# EEZ_Mosfet_pre-regulator_r3B3b.net
KiCad netlist of a schematic drawn in EAGLE
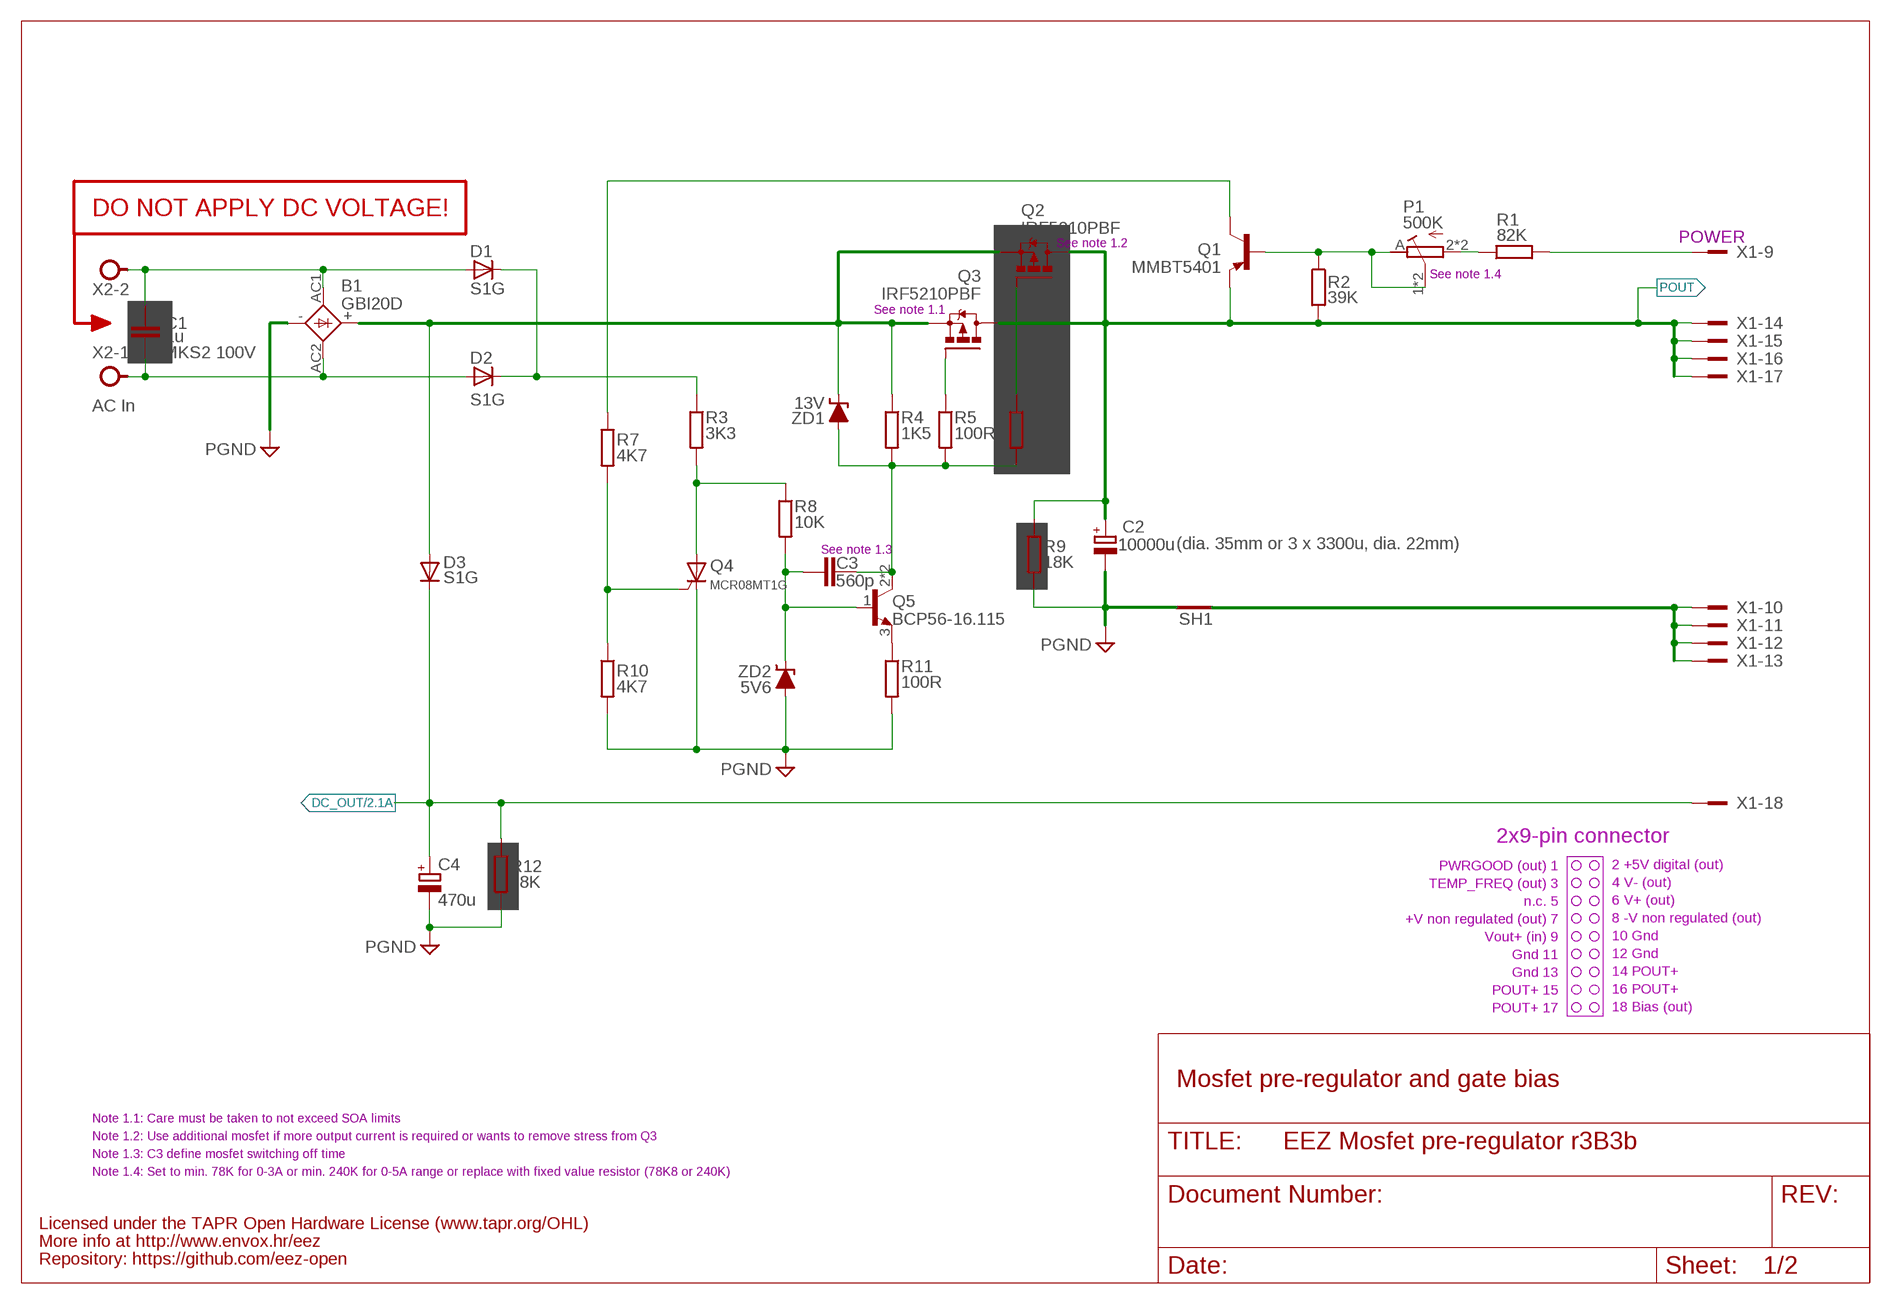
[diagram p0: schematic, sheet 1]
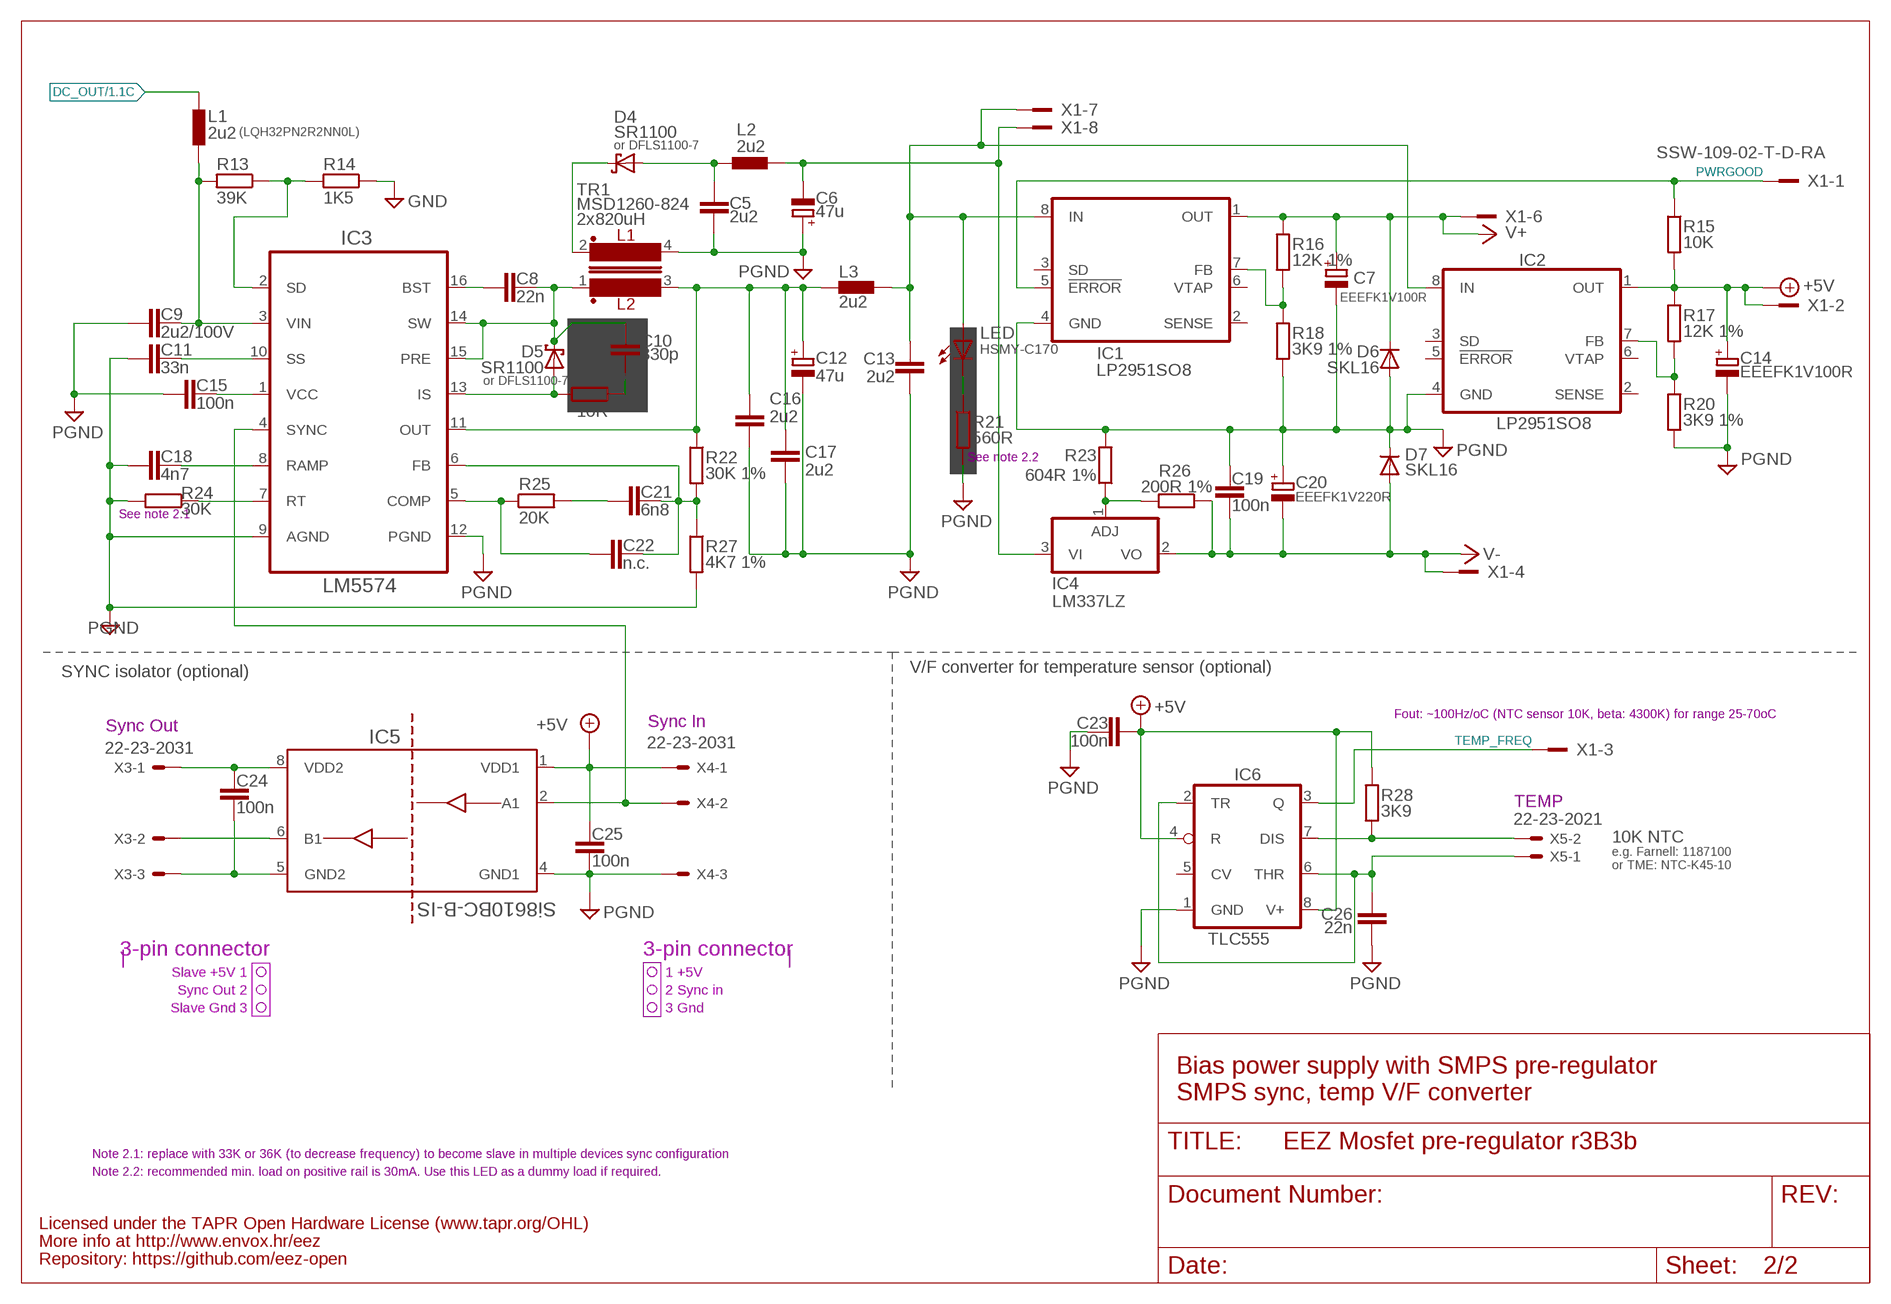
[diagram p1: schematic, sheet 2]

(export (version "E")
  (design (tool "Eeschema 10.0.6"))
  (components
    (comp (ref "C5")
      (value "2u2")
      (footprint "eagle-import:C1210")
      (libsource (lib "eagle-import") (part "C-EUC1210"))
    )
    (comp (ref "C6")
      (value "47u")
      (footprint "eagle-import:CAPAE660X610N_COMBO")
      (libsource (lib "eagle-import") (part "ECAPEEEFK+8.5MM"))
    )
    (comp (ref "C7")
      (value "EEEFK1V100R")
      (footprint "eagle-import:CAPAE430X610N_COMBO")
      (libsource (lib "eagle-import") (part "ECAPEEEFK+5MM"))
    )
    (comp (ref "C8")
      (value "22n")
      (footprint "eagle-import:C0805")
      (libsource (lib "eagle-import") (part "C-EUC0805"))
    )
    (comp (ref "C9")
      (value "2u2/100V")
      (footprint "eagle-import:C1210")
      (libsource (lib "eagle-import") (part "C-EUC1210"))
    )
    (comp (ref "C10")
      (value "330p")
      (footprint "eagle-import:C0805")
      (libsource (lib "eagle-import") (part "C-EUC0805"))
    )
    (comp (ref "C11")
      (value "33n")
      (footprint "eagle-import:C0805")
      (libsource (lib "eagle-import") (part "C-EUC0805"))
    )
    (comp (ref "C12")
      (value "47u")
      (footprint "eagle-import:CAPAE660X610N_COMBO")
      (libsource (lib "eagle-import") (part "ECAPEEEFK+8.5MM"))
    )
    (comp (ref "C13")
      (value "2u2")
      (footprint "eagle-import:C1210")
      (libsource (lib "eagle-import") (part "C-EUC1210"))
    )
    (comp (ref "C14")
      (value "EEEFK1V100R")
      (footprint "eagle-import:CAPAE430X610N_COMBO")
      (libsource (lib "eagle-import") (part "ECAPEEEFK+5MM"))
    )
    (comp (ref "C15")
      (value "100n")
      (footprint "eagle-import:C0805")
      (libsource (lib "eagle-import") (part "C-EUC0805"))
    )
    (comp (ref "C16")
      (value "2u2")
      (footprint "eagle-import:C1210")
      (libsource (lib "eagle-import") (part "C-EUC1210"))
    )
    (comp (ref "C17")
      (value "2u2")
      (footprint "eagle-import:C1210")
      (libsource (lib "eagle-import") (part "C-EUC1210"))
    )
    (comp (ref "C18")
      (value "4n7")
      (footprint "eagle-import:C0805")
      (libsource (lib "eagle-import") (part "C-EUC0805"))
    )
    (comp (ref "C19")
      (value "100n")
      (footprint "eagle-import:C0805")
      (libsource (lib "eagle-import") (part "C-EUC0805"))
    )
    (comp (ref "C20")
      (value "EEEFK1V220R")
      (footprint "eagle-import:CAPAE430X610N_COMBO")
      (libsource (lib "eagle-import") (part "ECAPEEEFK+5MM"))
    )
    (comp (ref "C21")
      (value "6n8")
      (footprint "eagle-import:C0805")
      (libsource (lib "eagle-import") (part "C-EUC0805"))
    )
    (comp (ref "C22")
      (value "n.c.")
      (footprint "eagle-import:C0805")
      (libsource (lib "eagle-import") (part "C-EUC0805"))
    )
    (comp (ref "C23")
      (value "100n")
      (footprint "eagle-import:C0603")
      (libsource (lib "eagle-import") (part "C-EUC0603"))
    )
    (comp (ref "C24")
      (value "100n")
      (footprint "eagle-import:C0603")
      (libsource (lib "eagle-import") (part "C-EUC0603"))
    )
    (comp (ref "C25")
      (value "100n")
      (footprint "eagle-import:C0603")
      (libsource (lib "eagle-import") (part "C-EUC0603"))
    )
    (comp (ref "C26")
      (value "22n")
      (footprint "eagle-import:C0805")
      (libsource (lib "eagle-import") (part "C-EUC0805"))
    )
    (comp (ref "D4")
      (value "SR1100")
      (footprint "eagle-import:DO34+SOD123")
      (libsource (lib "eagle-import") (part "SCHOTTKYDO34+SOD123"))
    )
    (comp (ref "D5")
      (value "SR1100")
      (footprint "eagle-import:DO34+SOD123")
      (libsource (lib "eagle-import") (part "SCHOTTKYDO34+SOD123"))
    )
    (comp (ref "D6")
      (value "SKL16")
      (footprint "eagle-import:DO214AC")
      (libsource (lib "eagle-import") (part "DIODE-DO214AC"))
    )
    (comp (ref "D7")
      (value "SKL16")
      (footprint "eagle-import:DO214AC")
      (libsource (lib "eagle-import") (part "DIODE-DO214AC"))
    )
    (comp (ref "IC1")
      (value "LP2951SO8")
      (footprint "eagle-import:SOIC127P600X175-8N")
      (libsource (lib "eagle-import") (part "LP2951SO8"))
    )
    (comp (ref "IC2")
      (value "LP2951SO8")
      (footprint "eagle-import:SOIC127P600X175-8N")
      (libsource (lib "eagle-import") (part "LP2951SO8"))
    )
    (comp (ref "IC3")
      (value "LM5574")
      (footprint "eagle-import:SOP65P640X110-16N")
      (fields (field (name "MPN") "LM5574MT"))
      (libsource (lib "eagle-import") (part "LM5574"))
    )
    (comp (ref "IC4")
      (value "LM337LZ")
      (footprint "eagle-import:TO92")
      (libsource (lib "eagle-import") (part "337LZLM"))
    )
    (comp (ref "IC5")
      (value "Si8610BC-B-IS")
      (footprint "eagle-import:SOIC127P600X173-8N")
      (libsource (lib "eagle-import") (part "SI8610"))
    )
    (comp (ref "IC6")
      (value "TLC555")
      (footprint "eagle-import:SOIC127P600X175-8N")
      (libsource (lib "eagle-import") (part "LM555SOIC8"))
    )
    (comp (ref "L1")
      (value "2u2")
      (footprint "eagle-import:L1210_COMBO")
      (libsource (lib "eagle-import") (part "L1210COMBO"))
    )
    (comp (ref "L2")
      (value "2u2")
      (footprint "eagle-import:L1210_COMBO")
      (libsource (lib "eagle-import") (part "L1210COMBO"))
    )
    (comp (ref "L3")
      (value "2u2")
      (footprint "eagle-import:L1210_COMBO")
      (libsource (lib "eagle-import") (part "L1210COMBO"))
    )
    (comp (ref "LED")
      (value "HSMY-C170")
      (footprint "eagle-import:CHIPLED_0805")
      (libsource (lib "eagle-import") (part "LEDCHIPLED_0805"))
    )
    (comp (ref "R13")
      (value "39K")
      (footprint "eagle-import:R0805")
      (libsource (lib "eagle-import") (part "R-EU_R0805"))
    )
    (comp (ref "R14")
      (value "1K5")
      (footprint "eagle-import:R0805")
      (libsource (lib "eagle-import") (part "R-EU_R0805"))
    )
    (comp (ref "R15")
      (value "10K")
      (footprint "eagle-import:R0805")
      (libsource (lib "eagle-import") (part "R-EU_R0805"))
    )
    (comp (ref "R16")
      (value "12K 1%")
      (footprint "eagle-import:R0805")
      (libsource (lib "eagle-import") (part "R-EU_R0805"))
    )
    (comp (ref "R17")
      (value "12K 1%")
      (footprint "eagle-import:R0805")
      (libsource (lib "eagle-import") (part "R-EU_R0805"))
    )
    (comp (ref "R18")
      (value "3K9 1%")
      (footprint "eagle-import:R0805")
      (libsource (lib "eagle-import") (part "R-EU_R0805"))
    )
    (comp (ref "R19")
      (value "10R")
      (footprint "eagle-import:R1210")
      (libsource (lib "eagle-import") (part "R-EU_R1210"))
    )
    (comp (ref "R20")
      (value "3K9 1%")
      (footprint "eagle-import:R0805")
      (libsource (lib "eagle-import") (part "R-EU_R0805"))
    )
    (comp (ref "R21")
      (value "560R")
      (footprint "eagle-import:R0805")
      (libsource (lib "eagle-import") (part "R-EU_R0805"))
    )
    (comp (ref "R22")
      (value "30K 1%")
      (footprint "eagle-import:R0805")
      (libsource (lib "eagle-import") (part "R-EU_R0805"))
    )
    (comp (ref "R23")
      (value "604R 1%")
      (footprint "eagle-import:R0805")
      (libsource (lib "eagle-import") (part "R-EU_R0805"))
    )
    (comp (ref "R24")
      (value "30K")
      (footprint "eagle-import:R0805")
      (libsource (lib "eagle-import") (part "R-EU_R0805"))
    )
    (comp (ref "R25")
      (value "20K")
      (footprint "eagle-import:R0805")
      (libsource (lib "eagle-import") (part "R-EU_R0805"))
    )
    (comp (ref "R26")
      (value "200R 1%")
      (footprint "eagle-import:R0805")
      (libsource (lib "eagle-import") (part "R-EU_R0805"))
    )
    (comp (ref "R27")
      (value "4K7 1%")
      (footprint "eagle-import:R0805")
      (libsource (lib "eagle-import") (part "R-EU_R0805"))
    )
    (comp (ref "R28")
      (value "3K9")
      (footprint "eagle-import:R0805")
      (libsource (lib "eagle-import") (part "R-EU_R0805"))
    )
    (comp (ref "TR1")
      (value "MSD1260-824")
      (footprint "eagle-import:MSD1260")
      (libsource (lib "eagle-import") (part "COILCRAFT_MSD1260INV"))
    )
    (comp (ref "X1")
      (value "SSW-109-02-T-D-RA")
      (footprint "eagle-import:SSW-109-02-T-D-RA")
      (fields (field (name "FARNELL") "1804359"))
      (libsource (lib "eagle-import") (part "SSW-109-02-T-D-RA"))
    )
    (comp (ref "X3")
      (value "22-23-2031")
      (footprint "eagle-import:22-23-2031")
      (fields
        (field (name "MF") "MOLEX")
        (field (name "MF_1") "MOLEX")
        (field (name "MPN") "22-23-2031")
        (field (name "OC_FARNELL") "1462950")
        (field (name "OC_NEWARK") "30C0862")
      )
      (libsource (lib "eagle-import") (part "22-23-2031"))
    )
    (comp (ref "X4")
      (value "22-23-2031")
      (footprint "eagle-import:22-23-2031")
      (fields
        (field (name "MF") "MOLEX")
        (field (name "MF_1") "MOLEX")
        (field (name "MPN") "22-23-2031")
        (field (name "OC_FARNELL") "1462950")
        (field (name "OC_NEWARK") "30C0862")
      )
      (libsource (lib "eagle-import") (part "22-23-2031"))
    )
    (comp (ref "X5")
      (value "22-23-2021")
      (footprint "eagle-import:22-23-2021")
      (fields (field (name "MF") "MOLEX"))
      (libsource (lib "eagle-import") (part "22-23-2021"))
    )
    (comp (ref "B1")
      (value "GBI20D")
      (footprint "eagle-import:GBI20")
      (libsource (lib "eagle-import") (part "BRIDGEDIOTEC"))
    )
    (comp (ref "C1")
      (value "1u")
      (footprint "eagle-import:C050-075X075")
      (libsource (lib "eagle-import") (part "C-EU050-075X075"))
    )
    (comp (ref "C2")
      (value "10000u")
      (footprint "eagle-import:ED35D+3XED22.5_COMBO")
      (libsource (lib "eagle-import") (part "ECAP35+3X22.5"))
    )
    (comp (ref "C3")
      (value "560p")
      (footprint "eagle-import:C0805")
      (libsource (lib "eagle-import") (part "C-EUC0805"))
    )
    (comp (ref "C4")
      (value "470u")
      (footprint "eagle-import:ECAP5_13")
      (libsource (lib "eagle-import") (part "ECAP5G_13MM"))
    )
    (comp (ref "D1")
      (value "S1G")
      (footprint "eagle-import:DO214AC")
      (libsource (lib "eagle-import") (part "DIODE-DO214AC"))
    )
    (comp (ref "D2")
      (value "S1G")
      (footprint "eagle-import:DO214AC")
      (libsource (lib "eagle-import") (part "DIODE-DO214AC"))
    )
    (comp (ref "D3")
      (value "S1G")
      (footprint "eagle-import:DO214AC")
      (libsource (lib "eagle-import") (part "DIODE-DO214AC"))
    )
    (comp (ref "P1")
      (value "500K")
      (footprint "eagle-import:R_TRIM+R0805")
      (libsource (lib "eagle-import") (part "R_TRIM_MIX0805"))
    )
    (comp (ref "Q1")
      (value "MMBT5401")
      (footprint "eagle-import:SOT23-BEC")
      (libsource (lib "eagle-import") (part "-PNP-SOT23-BECBC856B"))
    )
    (comp (ref "Q2")
      (value "IRF5210PBF")
      (footprint "eagle-import:TO220B-VMOS")
      (libsource (lib "eagle-import") (part "IRF9640"))
    )
    (comp (ref "Q3")
      (value "IRF5210PBF")
      (footprint "eagle-import:TO220B-VMOS")
      (libsource (lib "eagle-import") (part "IRF9640"))
    )
    (comp (ref "Q4")
      (value "MCR08MT1G")
      (footprint "eagle-import:SOT230P700X180-4N")
      (libsource (lib "eagle-import") (part "MCR08MT1G"))
    )
    (comp (ref "Q5")
      (value "BCP56-16.115")
      (footprint "eagle-import:SOT230P700X180-4N")
      (libsource (lib "eagle-import") (part "BCP56"))
    )
    (comp (ref "R1")
      (value "82K")
      (footprint "eagle-import:R0805")
      (libsource (lib "eagle-import") (part "R-EU_R0805"))
    )
    (comp (ref "R2")
      (value "39K")
      (footprint "eagle-import:R0805")
      (libsource (lib "eagle-import") (part "R-EU_R0805"))
    )
    (comp (ref "R3")
      (value "3K3")
      (footprint "eagle-import:R0805")
      (libsource (lib "eagle-import") (part "R-EU_R0805"))
    )
    (comp (ref "R4")
      (value "1K5")
      (footprint "eagle-import:R0805")
      (libsource (lib "eagle-import") (part "R-EU_R0805"))
    )
    (comp (ref "R5")
      (value "100R")
      (footprint "eagle-import:R0805")
      (libsource (lib "eagle-import") (part "R-EU_R0805"))
    )
    (comp (ref "R6")
      (value "100R")
      (footprint "eagle-import:R0805")
      (libsource (lib "eagle-import") (part "R-EU_R0805"))
    )
    (comp (ref "R7")
      (value "4K7")
      (footprint "eagle-import:R0805")
      (libsource (lib "eagle-import") (part "R-EU_R0805"))
    )
    (comp (ref "R8")
      (value "10K")
      (footprint "eagle-import:R0805")
      (libsource (lib "eagle-import") (part "R-EU_R0805"))
    )
    (comp (ref "R9")
      (value "18K")
      (footprint "eagle-import:R0805")
      (libsource (lib "eagle-import") (part "R-EU_R0805"))
    )
    (comp (ref "R10")
      (value "4K7")
      (footprint "eagle-import:R0805")
      (libsource (lib "eagle-import") (part "R-EU_R0805"))
    )
    (comp (ref "R11")
      (value "100R")
      (footprint "eagle-import:R0805")
      (libsource (lib "eagle-import") (part "R-EU_R0805"))
    )
    (comp (ref "R12")
      (value "18K")
      (footprint "eagle-import:R0805")
      (libsource (lib "eagle-import") (part "R-EU_R0805"))
    )
    (comp (ref "SH1")
      (value "SHORTH")
      (footprint "eagle-import:SHORT_2")
      (libsource (lib "eagle-import") (part "SHORTH"))
    )
    (comp (ref "X2")
      (value "AC In")
      (footprint "eagle-import:TBLOCK5.0_2")
      (libsource (lib "eagle-import") (part "TBLOCK5.0_2A"))
    )
    (comp (ref "ZD1")
      (value "13V")
      (footprint "eagle-import:MINIMELF")
      (libsource (lib "eagle-import") (part "ZENER-DIODEMINIMELF"))
    )
    (comp (ref "ZD2")
      (value "5V6")
      (footprint "eagle-import:MINIMELF")
      (libsource (lib "eagle-import") (part "ZENER-DIODEMINIMELF"))
    )
  )
  (nets
    (net (code "1") (name "+5V") (class "Default")
      (node (ref "C14") (pin "1") (pinfunction "+_1") (pintype "passive"))
      (node (ref "C14") (pin "1.1") (pinfunction "+_1.1") (pintype "passive"))
      (node (ref "C23") (pin "1") (pinfunction "1_1") (pintype "passive"))
      (node (ref "C25") (pin "1") (pinfunction "1_1") (pintype "passive"))
      (node (ref "IC2") (pin "1") (pinfunction "OUT_1") (pintype "output"))
      (node (ref "IC5") (pin "1") (pinfunction "VDD1_1") (pintype "power_in"))
      (node (ref "IC6") (pin "4") (pinfunction "R_4") (pintype "input"))
      (node (ref "IC6") (pin "8") (pinfunction "V+_8") (pintype "power_in"))
      (node (ref "R15") (pin "2") (pinfunction "2_2") (pintype "passive"))
      (node (ref "R17") (pin "1") (pinfunction "1_1") (pintype "passive"))
      (node (ref "R28") (pin "2") (pinfunction "2_2") (pintype "passive"))
      (node (ref "X1") (pin "2") (pinfunction "KL_2") (pintype "passive"))
      (node (ref "X4") (pin "1") (pinfunction "S_1") (pintype "passive"))
    )
    (net (code "2") (name "DC_OUT") (class "Default")
      (node (ref "C4") (pin "+") (pinfunction "+_+") (pintype "passive"))
      (node (ref "D3") (pin "C") (pinfunction "C_C") (pintype "passive"))
      (node (ref "L1") (pin "1") (pinfunction "1_1") (pintype "passive"))
      (node (ref "L1") (pin "1.1") (pinfunction "1_1.1") (pintype "passive"))
      (node (ref "R12") (pin "1") (pinfunction "1_1") (pintype "passive"))
      (node (ref "X1") (pin "18") (pinfunction "KL_18") (pintype "passive"))
    )
    (net (code "3") (name "GND") (class "Default")
      (node (ref "B1") (pin "-") (pinfunction "-_-") (pintype "passive"))
      (node (ref "C11") (pin "2") (pinfunction "2_2") (pintype "passive"))
      (node (ref "C12") (pin "2") (pinfunction "-_2") (pintype "passive"))
      (node (ref "C12") (pin "2.1") (pinfunction "-_2.1") (pintype "passive"))
      (node (ref "C13") (pin "2") (pinfunction "2_2") (pintype "passive"))
      (node (ref "C14") (pin "2") (pinfunction "-_2") (pintype "passive"))
      (node (ref "C14") (pin "2.1") (pinfunction "-_2.1") (pintype "passive"))
      (node (ref "C15") (pin "1") (pinfunction "1_1") (pintype "passive"))
      (node (ref "C16") (pin "2") (pinfunction "2_2") (pintype "passive"))
      (node (ref "C17") (pin "2") (pinfunction "2_2") (pintype "passive"))
      (node (ref "C18") (pin "1") (pinfunction "1_1") (pintype "passive"))
      (node (ref "C19") (pin "1") (pinfunction "1_1") (pintype "passive"))
      (node (ref "C2") (pin "-") (pinfunction "-_-") (pintype "passive"))
      (node (ref "C2") (pin "-1") (pinfunction "-_-1") (pintype "passive"))
      (node (ref "C2") (pin "-2") (pinfunction "-_-2") (pintype "passive"))
      (node (ref "C2") (pin "-3") (pinfunction "-_-3") (pintype "passive"))
      (node (ref "C20") (pin "1") (pinfunction "+_1") (pintype "passive"))
      (node (ref "C20") (pin "1.1") (pinfunction "+_1.1") (pintype "passive"))
      (node (ref "C23") (pin "2") (pinfunction "2_2") (pintype "passive"))
      (node (ref "C25") (pin "2") (pinfunction "2_2") (pintype "passive"))
      (node (ref "C26") (pin "1") (pinfunction "1_1") (pintype "passive"))
      (node (ref "C4") (pin "-") (pinfunction "-_-") (pintype "passive"))
      (node (ref "C5") (pin "2") (pinfunction "2_2") (pintype "passive"))
      (node (ref "C6") (pin "1") (pinfunction "+_1") (pintype "passive"))
      (node (ref "C6") (pin "1.1") (pinfunction "+_1.1") (pintype "passive"))
      (node (ref "C7") (pin "2") (pinfunction "-_2") (pintype "passive"))
      (node (ref "C7") (pin "2.1") (pinfunction "-_2.1") (pintype "passive"))
      (node (ref "C9") (pin "2") (pinfunction "2_2") (pintype "passive"))
      (node (ref "D6") (pin "A") (pinfunction "A_A") (pintype "passive"))
      (node (ref "D7") (pin "C") (pinfunction "C_C") (pintype "passive"))
      (node (ref "IC1") (pin "4") (pinfunction "GND_4") (pintype "passive"))
      (node (ref "IC2") (pin "4") (pinfunction "GND_4") (pintype "passive"))
      (node (ref "IC3") (pin "12") (pinfunction "PGND_12") (pintype "passive"))
      (node (ref "IC3") (pin "9") (pinfunction "AGND_9") (pintype "passive"))
      (node (ref "IC5") (pin "4") (pinfunction "GND1_4") (pintype "power_in"))
      (node (ref "IC6") (pin "1") (pinfunction "GND_1") (pintype "power_in"))
      (node (ref "Q4") (pin "1") (pinfunction "C_1") (pintype "passive"))
      (node (ref "R10") (pin "2") (pinfunction "2_2") (pintype "passive"))
      (node (ref "R11") (pin "2") (pinfunction "2_2") (pintype "passive"))
      (node (ref "R12") (pin "2") (pinfunction "2_2") (pintype "passive"))
      (node (ref "R14") (pin "1") (pinfunction "1_1") (pintype "passive"))
      (node (ref "R18") (pin "2") (pinfunction "2_2") (pintype "passive"))
      (node (ref "R20") (pin "2") (pinfunction "2_2") (pintype "passive"))
      (node (ref "R21") (pin "2") (pinfunction "2_2") (pintype "passive"))
      (node (ref "R23") (pin "2") (pinfunction "2_2") (pintype "passive"))
      (node (ref "R24") (pin "2") (pinfunction "2_2") (pintype "passive"))
      (node (ref "R27") (pin "2") (pinfunction "2_2") (pintype "passive"))
      (node (ref "R9") (pin "2") (pinfunction "2_2") (pintype "passive"))
      (node (ref "SH1") (pin "2") (pinfunction "GND_B_2") (pintype "bidirectional"))
      (node (ref "TR1") (pin "4") (pinfunction "4_4") (pintype "passive"))
      (node (ref "X4") (pin "3") (pinfunction "S_3") (pintype "passive"))
      (node (ref "ZD2") (pin "A") (pinfunction "A_A") (pintype "passive"))
    )
    (net (code "4") (name "Net-(B1-Pad+)") (class "Default")
      (node (ref "B1") (pin "+") (pinfunction "+_+") (pintype "passive"))
      (node (ref "D3") (pin "A") (pinfunction "A_A") (pintype "passive"))
      (node (ref "Q2") (pin "S") (pinfunction "S_S") (pintype "passive"))
      (node (ref "Q3") (pin "S") (pinfunction "S_S") (pintype "passive"))
      (node (ref "R4") (pin "1") (pinfunction "1_1") (pintype "passive"))
      (node (ref "ZD1") (pin "C") (pinfunction "C_C") (pintype "passive"))
    )
    (net (code "5") (name "Net-(B1-PadAC2)") (class "Default")
      (node (ref "B1") (pin "AC2") (pinfunction "AC2_AC2") (pintype "passive"))
      (node (ref "C1") (pin "2") (pinfunction "2_2") (pintype "passive"))
      (node (ref "D2") (pin "A") (pinfunction "A_A") (pintype "passive"))
      (node (ref "X2") (pin "1") (pinfunction "1_1") (pintype "bidirectional"))
    )
    (net (code "6") (name "Net-(C3-Pad1)") (class "Default")
      (node (ref "C3") (pin "1") (pinfunction "1_1") (pintype "passive"))
      (node (ref "Q5") (pin "2") (pinfunction "C_2") (pintype "passive"))
      (node (ref "Q5") (pin "4") (pinfunction "C_4") (pintype "passive"))
      (node (ref "R4") (pin "2") (pinfunction "2_2") (pintype "passive"))
      (node (ref "R5") (pin "2") (pinfunction "2_2") (pintype "passive"))
      (node (ref "R6") (pin "2") (pinfunction "2_2") (pintype "passive"))
      (node (ref "ZD1") (pin "A") (pinfunction "A_A") (pintype "passive"))
    )
    (net (code "7") (name "Net-(C5-Pad1)") (class "Default")
      (node (ref "C5") (pin "1") (pinfunction "1_1") (pintype "passive"))
      (node (ref "D4") (pin "A") (pinfunction "A_A") (pintype "passive"))
      (node (ref "D4") (pin "A.1") (pinfunction "A_A.1") (pintype "passive"))
      (node (ref "L2") (pin "1") (pinfunction "1_1") (pintype "passive"))
      (node (ref "L2") (pin "1.1") (pinfunction "1_1.1") (pintype "passive"))
    )
    (net (code "8") (name "Net-(C10-Pad2)") (class "Default")
      (node (ref "C10") (pin "2") (pinfunction "2_2") (pintype "passive"))
      (node (ref "R19") (pin "2") (pinfunction "2_2") (pintype "passive"))
    )
    (net (code "9") (name "Net-(C21-Pad2)") (class "Default")
      (node (ref "C21") (pin "2") (pinfunction "2_2") (pintype "passive"))
      (node (ref "R25") (pin "2") (pinfunction "2_2") (pintype "passive"))
    )
    (net (code "10") (name "Net-(D1-PadC)") (class "Default")
      (node (ref "D1") (pin "C") (pinfunction "C_C") (pintype "passive"))
      (node (ref "D2") (pin "C") (pinfunction "C_C") (pintype "passive"))
      (node (ref "R3") (pin "1") (pinfunction "1_1") (pintype "passive"))
    )
    (net (code "11") (name "Net-(D4-C-PadC.1)") (class "Default")
      (node (ref "D4") (pin "C") (pinfunction "C_C") (pintype "passive"))
      (node (ref "D4") (pin "C.1") (pinfunction "C_C.1") (pintype "passive"))
      (node (ref "TR1") (pin "2") (pinfunction "2_2") (pintype "passive"))
    )
    (net (code "12") (name "Net-(IC1-FB)") (class "Default")
      (node (ref "IC1") (pin "7") (pinfunction "FB_7") (pintype "input"))
      (node (ref "R16") (pin "2") (pinfunction "2_2") (pintype "passive"))
      (node (ref "R18") (pin "1") (pinfunction "1_1") (pintype "passive"))
    )
    (net (code "13") (name "Net-(IC1-IN)") (class "Default")
      (node (ref "C13") (pin "1") (pinfunction "1_1") (pintype "passive"))
      (node (ref "IC1") (pin "8") (pinfunction "IN_8") (pintype "power_in"))
      (node (ref "IC2") (pin "8") (pinfunction "IN_8") (pintype "power_in"))
      (node (ref "L3") (pin "2") (pinfunction "2_2") (pintype "passive"))
      (node (ref "L3") (pin "2.1") (pinfunction "2_2.1") (pintype "passive"))
      (node (ref "LED") (pin "A") (pinfunction "A_A") (pintype "passive"))
      (node (ref "X1") (pin "7") (pinfunction "KL_7") (pintype "passive"))
    )
    (net (code "14") (name "Net-(IC2-FB)") (class "Default")
      (node (ref "IC2") (pin "7") (pinfunction "FB_7") (pintype "input"))
      (node (ref "R17") (pin "2") (pinfunction "2_2") (pintype "passive"))
      (node (ref "R20") (pin "1") (pinfunction "1_1") (pintype "passive"))
    )
    (net (code "15") (name "Net-(IC3-BST)") (class "Default")
      (node (ref "C8") (pin "2") (pinfunction "2_2") (pintype "passive"))
      (node (ref "IC3") (pin "16") (pinfunction "BST_16") (pintype "input"))
    )
    (net (code "16") (name "Net-(IC3-COMP)") (class "Default")
      (node (ref "C22") (pin "2") (pinfunction "2_2") (pintype "passive"))
      (node (ref "IC3") (pin "5") (pinfunction "COMP_5") (pintype "input"))
      (node (ref "R25") (pin "1") (pinfunction "1_1") (pintype "passive"))
    )
    (net (code "17") (name "Net-(IC3-FB)") (class "Default")
      (node (ref "C21") (pin "1") (pinfunction "1_1") (pintype "passive"))
      (node (ref "C22") (pin "1") (pinfunction "1_1") (pintype "passive"))
      (node (ref "IC3") (pin "6") (pinfunction "FB_6") (pintype "input"))
      (node (ref "R22") (pin "2") (pinfunction "2_2") (pintype "passive"))
      (node (ref "R27") (pin "1") (pinfunction "1_1") (pintype "passive"))
    )
    (net (code "18") (name "Net-(IC3-IS)") (class "Default")
      (node (ref "D5") (pin "A") (pinfunction "A_A") (pintype "passive"))
      (node (ref "D5") (pin "A.1") (pinfunction "A_A.1") (pintype "passive"))
      (node (ref "IC3") (pin "13") (pinfunction "IS_13") (pintype "input"))
      (node (ref "R19") (pin "1") (pinfunction "1_1") (pintype "passive"))
    )
    (net (code "19") (name "Net-(IC3-OUT)") (class "Default")
      (node (ref "C12") (pin "1") (pinfunction "+_1") (pintype "passive"))
      (node (ref "C12") (pin "1.1") (pinfunction "+_1.1") (pintype "passive"))
      (node (ref "C16") (pin "1") (pinfunction "1_1") (pintype "passive"))
      (node (ref "C17") (pin "1") (pinfunction "1_1") (pintype "passive"))
      (node (ref "IC3") (pin "11") (pinfunction "OUT_11") (pintype "output"))
      (node (ref "L3") (pin "1") (pinfunction "1_1") (pintype "passive"))
      (node (ref "L3") (pin "1.1") (pinfunction "1_1.1") (pintype "passive"))
      (node (ref "R22") (pin "1") (pinfunction "1_1") (pintype "passive"))
      (node (ref "TR1") (pin "3") (pinfunction "3_3") (pintype "passive"))
    )
    (net (code "20") (name "Net-(IC3-PRE)") (class "Default")
      (node (ref "C10") (pin "1") (pinfunction "1_1") (pintype "passive"))
      (node (ref "C8") (pin "1") (pinfunction "1_1") (pintype "passive"))
      (node (ref "D5") (pin "C") (pinfunction "C_C") (pintype "passive"))
      (node (ref "D5") (pin "C.1") (pinfunction "C_C.1") (pintype "passive"))
      (node (ref "IC3") (pin "14") (pinfunction "SW_14") (pintype "output"))
      (node (ref "IC3") (pin "15") (pinfunction "PRE_15") (pintype "input"))
      (node (ref "TR1") (pin "1") (pinfunction "1_1") (pintype "passive"))
    )
    (net (code "21") (name "Net-(IC3-RAMP)") (class "Default")
      (node (ref "C18") (pin "2") (pinfunction "2_2") (pintype "passive"))
      (node (ref "IC3") (pin "8") (pinfunction "RAMP_8") (pintype "input"))
    )
    (net (code "22") (name "Net-(IC3-RT)") (class "Default")
      (node (ref "IC3") (pin "7") (pinfunction "RT_7") (pintype "input"))
      (node (ref "R24") (pin "1") (pinfunction "1_1") (pintype "passive"))
    )
    (net (code "23") (name "Net-(IC3-SD)") (class "Default")
      (node (ref "IC3") (pin "2") (pinfunction "SD_2") (pintype "input"))
      (node (ref "R13") (pin "1") (pinfunction "1_1") (pintype "passive"))
      (node (ref "R14") (pin "2") (pinfunction "2_2") (pintype "passive"))
    )
    (net (code "24") (name "Net-(IC3-SS)") (class "Default")
      (node (ref "C11") (pin "1") (pinfunction "1_1") (pintype "passive"))
      (node (ref "IC3") (pin "10") (pinfunction "SS_10") (pintype "input"))
    )
    (net (code "25") (name "Net-(IC3-SYNC)") (class "Default")
      (node (ref "IC3") (pin "4") (pinfunction "SYNC_4") (pintype "input"))
      (node (ref "IC5") (pin "2") (pinfunction "A1_2") (pintype "input"))
      (node (ref "X4") (pin "2") (pinfunction "S_2") (pintype "passive"))
    )
    (net (code "26") (name "Net-(IC3-VCC)") (class "Default")
      (node (ref "C15") (pin "2") (pinfunction "2_2") (pintype "passive"))
      (node (ref "IC3") (pin "1") (pinfunction "VCC_1") (pintype "power_in"))
    )
    (net (code "27") (name "Net-(IC3-VIN)") (class "Default")
      (node (ref "C9") (pin "1") (pinfunction "1_1") (pintype "passive"))
      (node (ref "IC3") (pin "3") (pinfunction "VIN_3") (pintype "input"))
      (node (ref "L1") (pin "2") (pinfunction "2_2") (pintype "passive"))
      (node (ref "L1") (pin "2.1") (pinfunction "2_2.1") (pintype "passive"))
      (node (ref "R13") (pin "2") (pinfunction "2_2") (pintype "passive"))
    )
    (net (code "28") (name "Net-(IC4-ADJ)") (class "Default")
      (node (ref "IC4") (pin "1") (pinfunction "ADJ_1") (pintype "input"))
      (node (ref "R23") (pin "1") (pinfunction "1_1") (pintype "passive"))
      (node (ref "R26") (pin "2") (pinfunction "2_2") (pintype "passive"))
    )
    (net (code "29") (name "Net-(IC4-VI)") (class "Default")
      (node (ref "C6") (pin "2") (pinfunction "-_2") (pintype "passive"))
      (node (ref "C6") (pin "2.1") (pinfunction "-_2.1") (pintype "passive"))
      (node (ref "IC4") (pin "3") (pinfunction "VI_3") (pintype "input"))
      (node (ref "L2") (pin "2") (pinfunction "2_2") (pintype "passive"))
      (node (ref "L2") (pin "2.1") (pinfunction "2_2.1") (pintype "passive"))
      (node (ref "X1") (pin "8") (pinfunction "KL_8") (pintype "passive"))
    )
    (net (code "30") (name "Net-(IC5-B1)") (class "Default")
      (node (ref "IC5") (pin "6") (pinfunction "B1_6") (pintype "output"))
      (node (ref "X3") (pin "2") (pinfunction "S_2") (pintype "passive"))
    )
    (net (code "31") (name "Net-(IC5-GND2)") (class "Default")
      (node (ref "C24") (pin "2") (pinfunction "2_2") (pintype "passive"))
      (node (ref "IC5") (pin "5") (pinfunction "GND2_5") (pintype "power_in"))
      (node (ref "X3") (pin "3") (pinfunction "S_3") (pintype "passive"))
    )
    (net (code "32") (name "Net-(IC5-VDD2)") (class "Default")
      (node (ref "C24") (pin "1") (pinfunction "1_1") (pintype "passive"))
      (node (ref "IC5") (pin "8") (pinfunction "VDD2_8") (pintype "power_in"))
      (node (ref "X3") (pin "1") (pinfunction "S_1") (pintype "passive"))
    )
    (net (code "33") (name "Net-(IC6-DIS)") (class "Default")
      (node (ref "IC6") (pin "7") (pinfunction "DIS_7") (pintype "input"))
      (node (ref "R28") (pin "1") (pinfunction "1_1") (pintype "passive"))
      (node (ref "X5") (pin "2") (pinfunction "S_2") (pintype "passive"))
    )
    (net (code "34") (name "Net-(IC6-THR)") (class "Default")
      (node (ref "C26") (pin "2") (pinfunction "2_2") (pintype "passive"))
      (node (ref "IC6") (pin "2") (pinfunction "TR_2") (pintype "input"))
      (node (ref "IC6") (pin "6") (pinfunction "THR_6") (pintype "input"))
      (node (ref "X5") (pin "1") (pinfunction "S_1") (pintype "passive"))
    )
    (net (code "35") (name "Net-(LED-PadC)") (class "Default")
      (node (ref "LED") (pin "C") (pinfunction "C_C") (pintype "passive"))
      (node (ref "R21") (pin "1") (pinfunction "1_1") (pintype "passive"))
    )
    (net (code "36") (name "Net-(P1-E-Pad2)") (class "Default")
      (node (ref "P1") (pin "2") (pinfunction "E_2") (pintype "passive"))
      (node (ref "P1") (pin "E") (pinfunction "E_E") (pintype "passive"))
      (node (ref "R1") (pin "1") (pinfunction "1_1") (pintype "passive"))
    )
    (net (code "37") (name "Net-(P1-PadA)") (class "Default")
      (node (ref "P1") (pin "1") (pinfunction "S_1") (pintype "passive"))
      (node (ref "P1") (pin "A") (pinfunction "A_A") (pintype "passive"))
      (node (ref "P1") (pin "S") (pinfunction "S_S") (pintype "passive"))
      (node (ref "Q1") (pin "B") (pinfunction "B_B") (pintype "passive"))
      (node (ref "R2") (pin "1") (pinfunction "1_1") (pintype "passive"))
    )
    (net (code "38") (name "Net-(Q1-PadC)") (class "Default")
      (node (ref "Q1") (pin "C") (pinfunction "C_C") (pintype "passive"))
      (node (ref "R7") (pin "1") (pinfunction "1_1") (pintype "passive"))
    )
    (net (code "39") (name "Net-(Q2-PadG)") (class "Default")
      (node (ref "Q2") (pin "G") (pinfunction "G_G") (pintype "passive"))
      (node (ref "R6") (pin "1") (pinfunction "1_1") (pintype "passive"))
    )
    (net (code "40") (name "Net-(Q3-PadG)") (class "Default")
      (node (ref "Q3") (pin "G") (pinfunction "G_G") (pintype "passive"))
      (node (ref "R5") (pin "1") (pinfunction "1_1") (pintype "passive"))
    )
    (net (code "41") (name "Net-(Q4-A-Pad2)") (class "Default")
      (node (ref "Q4") (pin "2") (pinfunction "A_2") (pintype "passive"))
      (node (ref "Q4") (pin "4") (pinfunction "A_4") (pintype "passive"))
      (node (ref "R3") (pin "2") (pinfunction "2_2") (pintype "passive"))
      (node (ref "R8") (pin "1") (pinfunction "1_1") (pintype "passive"))
    )
    (net (code "42") (name "Net-(Q4-G)") (class "Default")
      (node (ref "Q4") (pin "3") (pinfunction "G_3") (pintype "passive"))
      (node (ref "R10") (pin "1") (pinfunction "1_1") (pintype "passive"))
      (node (ref "R7") (pin "2") (pinfunction "2_2") (pintype "passive"))
    )
    (net (code "43") (name "Net-(Q5-B)") (class "Default")
      (node (ref "C3") (pin "2") (pinfunction "2_2") (pintype "passive"))
      (node (ref "Q5") (pin "1") (pinfunction "B_1") (pintype "passive"))
      (node (ref "R8") (pin "2") (pinfunction "2_2") (pintype "passive"))
      (node (ref "ZD2") (pin "C") (pinfunction "C_C") (pintype "passive"))
    )
    (net (code "44") (name "Net-(Q5-E)") (class "Default")
      (node (ref "Q5") (pin "3") (pinfunction "E_3") (pintype "passive"))
      (node (ref "R11") (pin "1") (pinfunction "1_1") (pintype "passive"))
    )
    (net (code "45") (name "Net-(SH1-GND_A)") (class "Default")
      (node (ref "SH1") (pin "1") (pinfunction "GND_A_1") (pintype "bidirectional"))
      (node (ref "X1") (pin "10") (pinfunction "KL_10") (pintype "passive"))
      (node (ref "X1") (pin "11") (pinfunction "KL_11") (pintype "passive"))
      (node (ref "X1") (pin "12") (pinfunction "KL_12") (pintype "passive"))
      (node (ref "X1") (pin "13") (pinfunction "KL_13") (pintype "passive"))
    )
    (net (code "46") (name "Net-(X1R-KL)") (class "Default")
      (node (ref "R1") (pin "2") (pinfunction "2_2") (pintype "passive"))
      (node (ref "X1") (pin "9") (pinfunction "KL_9") (pintype "passive"))
    )
    (net (code "47") (name "Net-(X2B-1)") (class "Default")
      (node (ref "B1") (pin "AC1") (pinfunction "AC1_AC1") (pintype "passive"))
      (node (ref "C1") (pin "1") (pinfunction "1_1") (pintype "passive"))
      (node (ref "D1") (pin "A") (pinfunction "A_A") (pintype "passive"))
      (node (ref "X2") (pin "2") (pinfunction "1_2") (pintype "bidirectional"))
    )
    (net (code "48") (name "POUT") (class "Default")
      (node (ref "C2") (pin "+") (pinfunction "+_+") (pintype "passive"))
      (node (ref "C2") (pin "+2") (pinfunction "+_+2") (pintype "passive"))
      (node (ref "C2") (pin "+3") (pinfunction "+_+3") (pintype "passive"))
      (node (ref "Q1") (pin "E") (pinfunction "E_E") (pintype "passive"))
      (node (ref "Q2") (pin "D") (pinfunction "D_D") (pintype "passive"))
      (node (ref "Q3") (pin "D") (pinfunction "D_D") (pintype "passive"))
      (node (ref "R2") (pin "2") (pinfunction "2_2") (pintype "passive"))
      (node (ref "R9") (pin "1") (pinfunction "1_1") (pintype "passive"))
      (node (ref "X1") (pin "14") (pinfunction "KL_14") (pintype "passive"))
      (node (ref "X1") (pin "15") (pinfunction "KL_15") (pintype "passive"))
      (node (ref "X1") (pin "16") (pinfunction "KL_16") (pintype "passive"))
      (node (ref "X1") (pin "17") (pinfunction "KL_17") (pintype "passive"))
    )
    (net (code "49") (name "PWRGOOD") (class "Default")
      (node (ref "IC1") (pin "5") (pinfunction "~{ERROR}_5") (pintype "input"))
      (node (ref "R15") (pin "1") (pinfunction "1_1") (pintype "passive"))
      (node (ref "X1") (pin "1") (pinfunction "KL_1") (pintype "passive"))
    )
    (net (code "50") (name "TEMP_FREQ") (class "Default")
      (node (ref "IC6") (pin "3") (pinfunction "Q_3") (pintype "output"))
      (node (ref "X1") (pin "3") (pinfunction "KL_3") (pintype "passive"))
    )
    (net (code "51") (name "V+") (class "Default")
      (node (ref "C7") (pin "1") (pinfunction "+_1") (pintype "passive"))
      (node (ref "C7") (pin "1.1") (pinfunction "+_1.1") (pintype "passive"))
      (node (ref "D6") (pin "C") (pinfunction "C_C") (pintype "passive"))
      (node (ref "IC1") (pin "1") (pinfunction "OUT_1") (pintype "output"))
      (node (ref "R16") (pin "1") (pinfunction "1_1") (pintype "passive"))
      (node (ref "X1") (pin "6") (pinfunction "KL_6") (pintype "passive"))
    )
    (net (code "52") (name "V-") (class "Default")
      (node (ref "C19") (pin "2") (pinfunction "2_2") (pintype "passive"))
      (node (ref "C20") (pin "2") (pinfunction "-_2") (pintype "passive"))
      (node (ref "C20") (pin "2.1") (pinfunction "-_2.1") (pintype "passive"))
      (node (ref "D7") (pin "A") (pinfunction "A_A") (pintype "passive"))
      (node (ref "IC4") (pin "2") (pinfunction "VO_2") (pintype "passive"))
      (node (ref "R26") (pin "1") (pinfunction "1_1") (pintype "passive"))
      (node (ref "X1") (pin "4") (pinfunction "KL_4") (pintype "passive"))
    )
    (net (code "53") (name "unconnected-(IC1-SD-Pad3)") (class "Default")
      (node (ref "IC1") (pin "3") (pinfunction "SD_3") (pintype "input"))
    )
    (net (code "54") (name "unconnected-(IC1-SENSE-Pad2)") (class "Default")
      (node (ref "IC1") (pin "2") (pinfunction "SENSE_2") (pintype "input"))
    )
    (net (code "55") (name "unconnected-(IC1-VTAP-Pad6)") (class "Default")
      (node (ref "IC1") (pin "6") (pinfunction "VTAP_6") (pintype "input"))
    )
    (net (code "56") (name "unconnected-(IC2-SD-Pad3)") (class "Default")
      (node (ref "IC2") (pin "3") (pinfunction "SD_3") (pintype "input"))
    )
    (net (code "57") (name "unconnected-(IC2-SENSE-Pad2)") (class "Default")
      (node (ref "IC2") (pin "2") (pinfunction "SENSE_2") (pintype "input"))
    )
    (net (code "58") (name "unconnected-(IC2-VTAP-Pad6)") (class "Default")
      (node (ref "IC2") (pin "6") (pinfunction "VTAP_6") (pintype "input"))
    )
    (net (code "59") (name "unconnected-(IC2-~{ERROR}-Pad5)") (class "Default")
      (node (ref "IC2") (pin "5") (pinfunction "~{ERROR}_5") (pintype "input"))
    )
    (net (code "60") (name "unconnected-(IC6-CV-Pad5)") (class "Default")
      (node (ref "IC6") (pin "5") (pinfunction "CV_5") (pintype "input"))
    )
  )
)
